# home_alarm_revB.net
KiCad netlist of a schematic drawn in EAGLE
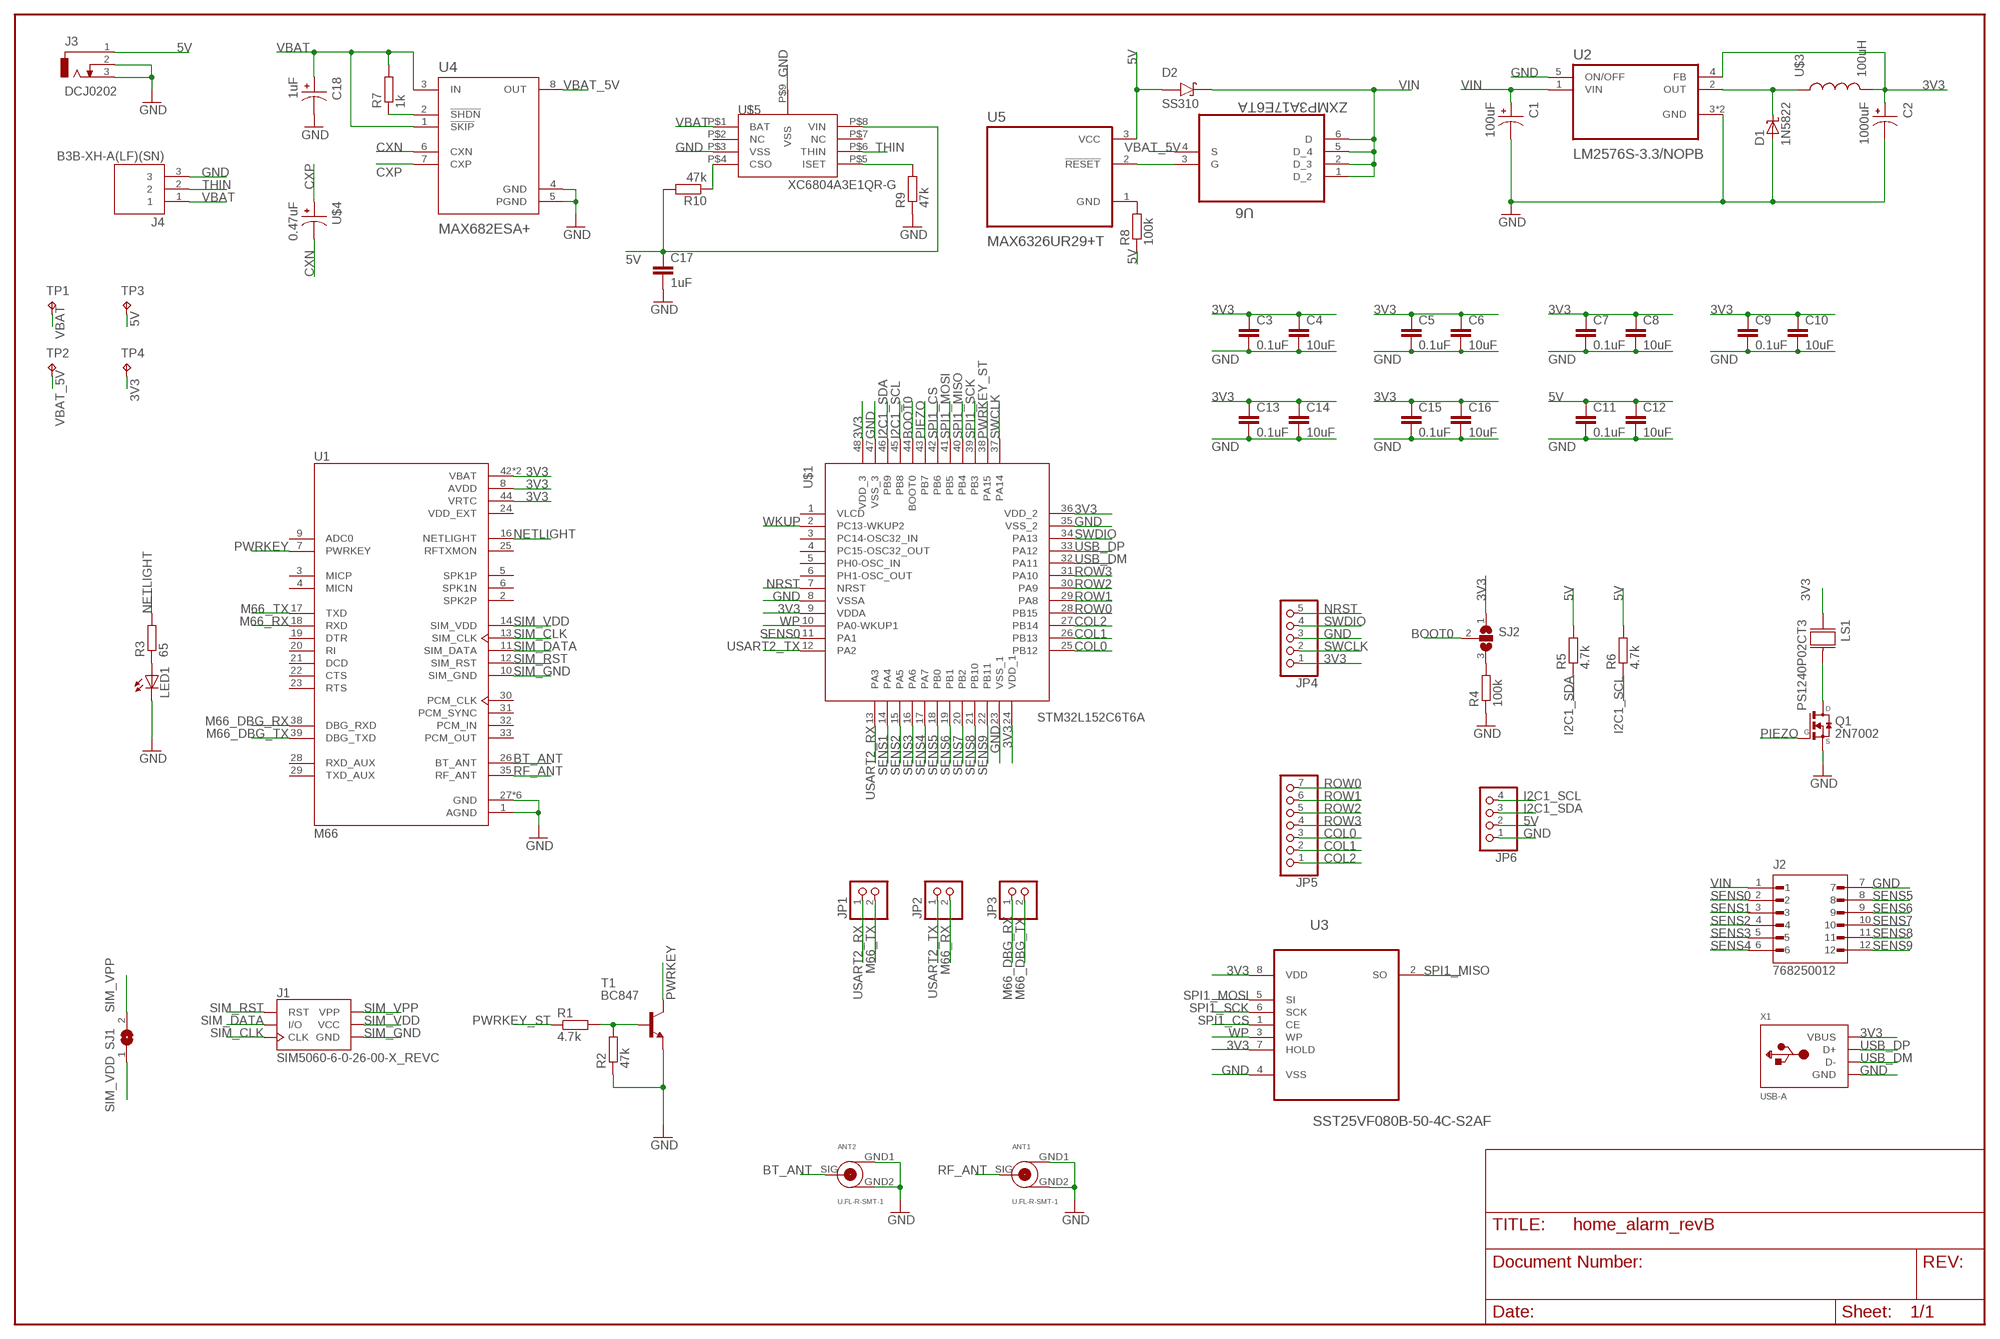
[diagram p0: schematic, sheet 1]

(export (version "E")
  (design (tool "Eeschema 10.0.6"))
  (components
    (comp (ref "ANT1")
      (value "U.FL-R-SMT-1")
      (footprint "eagle-import:U.FL-R-SMT-1")
      (fields (field (name "MF") "Hirose Electric Co Ltd"))
      (libsource (lib "eagle-import") (part "U.FL-R-SMT-1"))
    )
    (comp (ref "ANT2")
      (value "U.FL-R-SMT-1")
      (footprint "eagle-import:U.FL-R-SMT-1")
      (fields (field (name "MF") "Hirose Electric Co Ltd"))
      (libsource (lib "eagle-import") (part "U.FL-R-SMT-1"))
    )
    (comp (ref "C1")
      (value "100uF")
      (footprint "eagle-import:CAP_EEEFP1C101AV")
      (fields (field (name "MF") "Panasonic") (field (name "MP") "EEEFP1C101AV"))
      (libsource (lib "eagle-import") (part "EEEFP1C101AV"))
    )
    (comp (ref "C2")
      (value "1000uF")
      (footprint "eagle-import:CAP_EEEFK1C102SV")
      (fields (field (name "MF") "Panasonic") (field (name "MP") "EEEFK1C102SV"))
      (libsource (lib "eagle-import") (part "EEEFK1C102SV"))
    )
    (comp (ref "C3")
      (value "0.1uF")
      (footprint "eagle-import:C0805")
      (libsource (lib "eagle-import") (part "C-EUC0805"))
    )
    (comp (ref "C4")
      (value "10uF")
      (footprint "eagle-import:C0805")
      (libsource (lib "eagle-import") (part "C-EUC0805"))
    )
    (comp (ref "C5")
      (value "0.1uF")
      (footprint "eagle-import:C0805")
      (libsource (lib "eagle-import") (part "C-EUC0805"))
    )
    (comp (ref "C6")
      (value "10uF")
      (footprint "eagle-import:C0805")
      (libsource (lib "eagle-import") (part "C-EUC0805"))
    )
    (comp (ref "C7")
      (value "0.1uF")
      (footprint "eagle-import:C0805")
      (libsource (lib "eagle-import") (part "C-EUC0805"))
    )
    (comp (ref "C8")
      (value "10uF")
      (footprint "eagle-import:C0805")
      (libsource (lib "eagle-import") (part "C-EUC0805"))
    )
    (comp (ref "C9")
      (value "0.1uF")
      (footprint "eagle-import:C0805")
      (libsource (lib "eagle-import") (part "C-EUC0805"))
    )
    (comp (ref "C10")
      (value "10uF")
      (footprint "eagle-import:C0805")
      (libsource (lib "eagle-import") (part "C-EUC0805"))
    )
    (comp (ref "C11")
      (value "0.1uF")
      (footprint "eagle-import:C0805")
      (libsource (lib "eagle-import") (part "C-EUC0805"))
    )
    (comp (ref "C12")
      (value "10uF")
      (footprint "eagle-import:C0805")
      (libsource (lib "eagle-import") (part "C-EUC0805"))
    )
    (comp (ref "C13")
      (value "0.1uF")
      (footprint "eagle-import:C0805")
      (libsource (lib "eagle-import") (part "C-EUC0805"))
    )
    (comp (ref "C14")
      (value "10uF")
      (footprint "eagle-import:C0805")
      (libsource (lib "eagle-import") (part "C-EUC0805"))
    )
    (comp (ref "C15")
      (value "0.1uF")
      (footprint "eagle-import:C0805")
      (libsource (lib "eagle-import") (part "C-EUC0805"))
    )
    (comp (ref "C16")
      (value "10uF")
      (footprint "eagle-import:C0805")
      (libsource (lib "eagle-import") (part "C-EUC0805"))
    )
    (comp (ref "C17")
      (value "1uF")
      (footprint "eagle-import:C0805")
      (libsource (lib "eagle-import") (part "C-EUC0805"))
    )
    (comp (ref "C18")
      (value "1uF")
      (footprint "eagle-import:CAP_EEE1HA010NR")
      (fields (field (name "MF") "Panasonic Electronic") (field (name "MP") "EEE-1HA010NR"))
      (libsource (lib "eagle-import") (part "EEE1HA010NR"))
    )
    (comp (ref "D1")
      (value "1N5822")
      (footprint "eagle-import:DIOAD2120W130L950D530P")
      (fields (field (name "MF") "EIC"))
      (libsource (lib "eagle-import") (part "1N5822"))
    )
    (comp (ref "D2")
      (value "SS310")
      (footprint "eagle-import:DIOM6859X262N")
      (fields (field (name "MF") "Taiwan Semiconductor"))
      (libsource (lib "eagle-import") (part "SS310"))
    )
    (comp (ref "J1")
      (value "SIM5060-6-0-26-00-X_REVC")
      (footprint "eagle-import:GCT_SIM5060-6-0-26-00-X_REVC")
      (fields (field (name "MF") "Global Connector Technology") (field (name "MP") "SIM5060-6-0-26-00-A"))
      (libsource (lib "eagle-import") (part "SIM5060-6-0-26-00-X_REVC"))
    )
    (comp (ref "J2")
      (value "768250012")
      (footprint "eagle-import:MOLEX_768250012")
      (fields (field (name "MF") "Molex") (field (name "MP") "76825-0012"))
      (libsource (lib "eagle-import") (part "768250012"))
    )
    (comp (ref "J3")
      (value "DCJ0202")
      (footprint "eagle-import:DCJ0202")
      (libsource (lib "eagle-import") (part "DCJ0202"))
    )
    (comp (ref "J4")
      (value "B3B-XH-A(LF)(SN)")
      (footprint "eagle-import:JST_B3B-XH-A(LF)(SN)")
      (fields (field (name "MF") "JST Sales"))
      (libsource (lib "eagle-import") (part "B3B-XH-A(LF)(SN)"))
    )
    (comp (ref "JP1")
      (value "PINHD-1X2")
      (footprint "eagle-import:1X02")
      (libsource (lib "eagle-import") (part "PINHD-1X2"))
    )
    (comp (ref "JP2")
      (value "PINHD-1X2")
      (footprint "eagle-import:1X02")
      (libsource (lib "eagle-import") (part "PINHD-1X2"))
    )
    (comp (ref "JP3")
      (value "PINHD-1X2")
      (footprint "eagle-import:1X02")
      (libsource (lib "eagle-import") (part "PINHD-1X2"))
    )
    (comp (ref "JP4")
      (value "PINHD-1X5")
      (footprint "eagle-import:1X05")
      (libsource (lib "eagle-import") (part "PINHD-1X5"))
    )
    (comp (ref "JP5")
      (value "PINHD-1X7")
      (footprint "eagle-import:1X07")
      (libsource (lib "eagle-import") (part "PINHD-1X7"))
    )
    (comp (ref "JP6")
      (value "PINHD-1X4")
      (footprint "eagle-import:1X04")
      (libsource (lib "eagle-import") (part "PINHD-1X4"))
    )
    (comp (ref "LED1")
      (value "LEDCHIPLED_0603")
      (footprint "eagle-import:CHIPLED_0603")
      (libsource (lib "eagle-import") (part "LEDCHIPLED_0603"))
    )
    (comp (ref "LS1")
      (value "PS1240P02CT3")
      (footprint "eagle-import:XDCR_PS1240P02CT3")
      (fields (field (name "MF") "TDK"))
      (libsource (lib "eagle-import") (part "PS1240P02CT3"))
    )
    (comp (ref "Q1")
      (value "2N7002")
      (footprint "eagle-import:SOT23")
      (fields (field (name "MF") "STMicroelectronics") (field (name "MP") "2N-7002"))
      (libsource (lib "eagle-import") (part "2N7002"))
    )
    (comp (ref "R1")
      (value "4.7k")
      (footprint "eagle-import:R0805")
      (libsource (lib "eagle-import") (part "R-EU_R0805"))
    )
    (comp (ref "R2")
      (value "47k")
      (footprint "eagle-import:R0805")
      (libsource (lib "eagle-import") (part "R-EU_R0805"))
    )
    (comp (ref "R3")
      (value "65")
      (footprint "eagle-import:R0805")
      (libsource (lib "eagle-import") (part "R-EU_R0805"))
    )
    (comp (ref "R4")
      (value "100k")
      (footprint "eagle-import:R0805")
      (libsource (lib "eagle-import") (part "R-EU_R0805"))
    )
    (comp (ref "R5")
      (value "4.7k")
      (footprint "eagle-import:R0805")
      (libsource (lib "eagle-import") (part "R-EU_R0805"))
    )
    (comp (ref "R6")
      (value "4.7k")
      (footprint "eagle-import:R0805")
      (libsource (lib "eagle-import") (part "R-EU_R0805"))
    )
    (comp (ref "R7")
      (value "1k")
      (footprint "eagle-import:R0805")
      (libsource (lib "eagle-import") (part "R-EU_R0805"))
    )
    (comp (ref "R8")
      (value "100k")
      (footprint "eagle-import:R0805")
      (libsource (lib "eagle-import") (part "R-EU_R0805"))
    )
    (comp (ref "R9")
      (value "47k")
      (footprint "eagle-import:R0805")
      (libsource (lib "eagle-import") (part "R-EU_R0805"))
    )
    (comp (ref "R10")
      (value "47k")
      (footprint "eagle-import:R0805")
      (libsource (lib "eagle-import") (part "R-EU_R0805"))
    )
    (comp (ref "SJ1") (value "SJ") (footprint "eagle-import:SJ") (libsource (lib "eagle-import") (part "SJ")))
    (comp (ref "SJ2")
      (value "SJ2W")
      (footprint "eagle-import:SJ_2")
      (libsource (lib "eagle-import") (part "SJ2W"))
    )
    (comp (ref "T1")
      (value "BC847")
      (footprint "eagle-import:SOT23")
      (libsource (lib "eagle-import") (part "BC847"))
    )
    (comp (ref "TP1")
      (value "TPB1,27")
      (footprint "eagle-import:B1,27")
      (libsource (lib "eagle-import") (part "TPB1,27"))
    )
    (comp (ref "TP2")
      (value "TPB1,27")
      (footprint "eagle-import:B1,27")
      (libsource (lib "eagle-import") (part "TPB1,27"))
    )
    (comp (ref "TP3")
      (value "TPB1,27")
      (footprint "eagle-import:B1,27")
      (libsource (lib "eagle-import") (part "TPB1,27"))
    )
    (comp (ref "TP4")
      (value "TPB1,27")
      (footprint "eagle-import:B1,27")
      (libsource (lib "eagle-import") (part "TPB1,27"))
    )
    (comp (ref "U$1")
      (value "STM32L152C6T6A")
      (footprint "eagle-import:STM32L152C6T6A")
      (libsource (lib "eagle-import") (part "STM32L152C6T6A"))
    )
    (comp (ref "U$3")
      (value "100uH")
      (footprint "eagle-import:MSS1210-104KED")
      (libsource (lib "eagle-import") (part "MSS1210-104KED"))
    )
    (comp (ref "U$4")
      (value "0.47uF")
      (footprint "eagle-import:865230640004")
      (libsource (lib "eagle-import") (part "865230640004"))
    )
    (comp (ref "U$5")
      (value "XC6804A3E1QR-G")
      (footprint "eagle-import:XC6804A3E1QR-G")
      (libsource (lib "eagle-import") (part "XC6804A3E1QR-G"))
    )
    (comp (ref "U1")
      (value "M66")
      (footprint "eagle-import:XCVR_M66")
      (fields (field (name "MF") "Quectel"))
      (libsource (lib "eagle-import") (part "M66"))
    )
    (comp (ref "U2")
      (value "LM2576S-3.3/NOPB")
      (footprint "eagle-import:VREG_TPS79625KTTR")
      (fields (field (name "MF") "Texas Instruments"))
      (libsource (lib "eagle-import") (part "LM2576S-3.3/NOPB"))
    )
    (comp (ref "U3")
      (value "SST25VF080B-50-4C-S2AF")
      (footprint "eagle-import:SOIC127P790X216-8N")
      (fields (field (name "MF") "Microchip"))
      (libsource (lib "eagle-import") (part "SST25VF080B-50-4C-S2AF"))
    )
    (comp (ref "U4")
      (value "MAX682ESA+")
      (footprint "eagle-import:SOIC127P600X175-8N")
      (fields (field (name "MF") "Maxim Integrated"))
      (libsource (lib "eagle-import") (part "MAX682ESA+"))
    )
    (comp (ref "U5")
      (value "MAX6326UR29+T")
      (footprint "eagle-import:SOT95P237X112-3N")
      (fields (field (name "MF") "Maxim Integrated"))
      (libsource (lib "eagle-import") (part "MAX6326UR29+T"))
    )
    (comp (ref "U6")
      (value "ZXMP3A17E6TA")
      (footprint "eagle-import:SOT95P280X145-6N")
      (fields (field (name "MF") "Diodes Inc."))
      (libsource (lib "eagle-import") (part "ZXMP3A17E6TA"))
    )
    (comp (ref "X1")
      (value "USB-A")
      (footprint "eagle-import:MOLEX_480371000")
      (libsource (lib "eagle-import") (part "USB-A"))
    )
  )
  (nets
    (net (code "1") (name "/3V3") (class "Default")
      (node (ref "C10") (pin "1") (pinfunction "1_1") (pintype "passive"))
      (node (ref "C13") (pin "1") (pinfunction "1_1") (pintype "passive"))
      (node (ref "C14") (pin "1") (pinfunction "1_1") (pintype "passive"))
      (node (ref "C15") (pin "1") (pinfunction "1_1") (pintype "passive"))
      (node (ref "C16") (pin "1") (pinfunction "1_1") (pintype "passive"))
      (node (ref "C2") (pin "1") (pinfunction "1_1") (pintype "passive"))
      (node (ref "C3") (pin "1") (pinfunction "1_1") (pintype "passive"))
      (node (ref "C4") (pin "1") (pinfunction "1_1") (pintype "passive"))
      (node (ref "C5") (pin "1") (pinfunction "1_1") (pintype "passive"))
      (node (ref "C6") (pin "1") (pinfunction "1_1") (pintype "passive"))
      (node (ref "C7") (pin "1") (pinfunction "1_1") (pintype "passive"))
      (node (ref "C8") (pin "1") (pinfunction "1_1") (pintype "passive"))
      (node (ref "C9") (pin "1") (pinfunction "1_1") (pintype "passive"))
      (node (ref "JP4") (pin "1") (pinfunction "1_1") (pintype "passive"))
      (node (ref "LS1") (pin "1") (pinfunction "1_1") (pintype "passive"))
      (node (ref "SJ2") (pin "1") (pinfunction "1_1") (pintype "passive"))
      (node (ref "TP4") (pin "TP") (pinfunction "TP_TP") (pintype "input"))
      (node (ref "U$1") (pin "24") (pinfunction "VDD_1_24") (pintype "bidirectional"))
      (node (ref "U$1") (pin "36") (pinfunction "VDD_2_36") (pintype "bidirectional"))
      (node (ref "U$1") (pin "48") (pinfunction "VDD_3_48") (pintype "bidirectional"))
      (node (ref "U$1") (pin "9") (pinfunction "VDDA_9") (pintype "bidirectional"))
      (node (ref "U$3") (pin "P$2") (pinfunction "2_P$2") (pintype "passive"))
      (node (ref "U1") (pin "42") (pinfunction "VBAT_42") (pintype "power_in"))
      (node (ref "U1") (pin "43") (pinfunction "VBAT_43") (pintype "power_in"))
      (node (ref "U1") (pin "44") (pinfunction "VRTC_44") (pintype "power_in"))
      (node (ref "U1") (pin "8") (pinfunction "AVDD_8") (pintype "power_in"))
      (node (ref "U2") (pin "4") (pinfunction "FB_4") (pintype "output"))
      (node (ref "U3") (pin "7") (pinfunction "HOLD_7") (pintype "input"))
      (node (ref "U3") (pin "8") (pinfunction "VDD_8") (pintype "power_in"))
      (node (ref "X1") (pin "1") (pinfunction "VBUS_1") (pintype "power_in"))
    )
    (net (code "2") (name "/5V") (class "Default")
      (node (ref "C11") (pin "1") (pinfunction "1_1") (pintype "passive"))
      (node (ref "C12") (pin "1") (pinfunction "1_1") (pintype "passive"))
      (node (ref "C17") (pin "1") (pinfunction "1_1") (pintype "passive"))
      (node (ref "D2") (pin "A") (pinfunction "A_A") (pintype "passive"))
      (node (ref "J3") (pin "1") (pinfunction "1_1") (pintype "passive"))
      (node (ref "JP6") (pin "2") (pinfunction "2_2") (pintype "passive"))
      (node (ref "R10") (pin "2") (pinfunction "2_2") (pintype "passive"))
      (node (ref "R5") (pin "2") (pinfunction "2_2") (pintype "passive"))
      (node (ref "R6") (pin "2") (pinfunction "2_2") (pintype "passive"))
      (node (ref "R8") (pin "1") (pinfunction "1_1") (pintype "passive"))
      (node (ref "TP3") (pin "TP") (pinfunction "TP_TP") (pintype "input"))
      (node (ref "U$5") (pin "P$8") (pinfunction "VIN_P$8") (pintype "bidirectional"))
      (node (ref "U5") (pin "3") (pinfunction "VCC_3") (pintype "power_in"))
    )
    (net (code "3") (name "/BOOT0") (class "Default")
      (node (ref "SJ2") (pin "2") (pinfunction "2_2") (pintype "passive"))
      (node (ref "U$1") (pin "44") (pinfunction "BOOT0_44") (pintype "bidirectional"))
    )
    (net (code "4") (name "/BT_ANT") (class "Default")
      (node (ref "ANT2") (pin "SIG") (pinfunction "SIG_SIG") (pintype "bidirectional"))
      (node (ref "U1") (pin "26") (pinfunction "BT_ANT_26") (pintype "bidirectional"))
    )
    (net (code "5") (name "/COL0") (class "Default")
      (node (ref "JP5") (pin "3") (pinfunction "3_3") (pintype "passive"))
      (node (ref "U$1") (pin "25") (pinfunction "PB12_25") (pintype "bidirectional"))
    )
    (net (code "6") (name "/COL1") (class "Default")
      (node (ref "JP5") (pin "2") (pinfunction "2_2") (pintype "passive"))
      (node (ref "U$1") (pin "26") (pinfunction "PB13_26") (pintype "bidirectional"))
    )
    (net (code "7") (name "/COL2") (class "Default")
      (node (ref "JP5") (pin "1") (pinfunction "1_1") (pintype "passive"))
      (node (ref "U$1") (pin "27") (pinfunction "PB14_27") (pintype "bidirectional"))
    )
    (net (code "8") (name "/CXN") (class "Default")
      (node (ref "U$4") (pin "2") (pinfunction "2_2") (pintype "passive"))
      (node (ref "U4") (pin "6") (pinfunction "CXN_6") (pintype "passive"))
    )
    (net (code "9") (name "/CXP") (class "Default")
      (node (ref "U$4") (pin "1") (pinfunction "1_1") (pintype "passive"))
      (node (ref "U4") (pin "7") (pinfunction "CXP_7") (pintype "passive"))
    )
    (net (code "10") (name "/I2C1_SCL") (class "Default")
      (node (ref "JP6") (pin "4") (pinfunction "4_4") (pintype "passive"))
      (node (ref "R6") (pin "1") (pinfunction "1_1") (pintype "passive"))
      (node (ref "U$1") (pin "45") (pinfunction "PB8_45") (pintype "bidirectional"))
    )
    (net (code "11") (name "/I2C1_SDA") (class "Default")
      (node (ref "JP6") (pin "3") (pinfunction "3_3") (pintype "passive"))
      (node (ref "R5") (pin "1") (pinfunction "1_1") (pintype "passive"))
      (node (ref "U$1") (pin "46") (pinfunction "PB9_46") (pintype "bidirectional"))
    )
    (net (code "12") (name "/M66_DBG_RX") (class "Default")
      (node (ref "JP3") (pin "1") (pinfunction "1_1") (pintype "passive"))
      (node (ref "U1") (pin "38") (pinfunction "DBG_RXD_38") (pintype "input"))
    )
    (net (code "13") (name "/M66_DBG_TX") (class "Default")
      (node (ref "JP3") (pin "2") (pinfunction "2_2") (pintype "passive"))
      (node (ref "U1") (pin "39") (pinfunction "DBG_TXD_39") (pintype "output"))
    )
    (net (code "14") (name "/M66_RX") (class "Default")
      (node (ref "JP2") (pin "2") (pinfunction "2_2") (pintype "passive"))
      (node (ref "U1") (pin "18") (pinfunction "RXD_18") (pintype "input"))
    )
    (net (code "15") (name "/M66_TX") (class "Default")
      (node (ref "JP1") (pin "2") (pinfunction "2_2") (pintype "passive"))
      (node (ref "U1") (pin "17") (pinfunction "TXD_17") (pintype "output"))
    )
    (net (code "16") (name "/NETLIGHT") (class "Default")
      (node (ref "R3") (pin "2") (pinfunction "2_2") (pintype "passive"))
      (node (ref "U1") (pin "16") (pinfunction "NETLIGHT_16") (pintype "output"))
    )
    (net (code "17") (name "/NRST") (class "Default")
      (node (ref "JP4") (pin "5") (pinfunction "5_5") (pintype "passive"))
      (node (ref "U$1") (pin "7") (pinfunction "NRST_7") (pintype "bidirectional"))
    )
    (net (code "18") (name "/PIEZO") (class "Default")
      (node (ref "Q1") (pin "1") (pinfunction "G_1") (pintype "passive"))
      (node (ref "U$1") (pin "43") (pinfunction "PB7_43") (pintype "bidirectional"))
    )
    (net (code "19") (name "/PWRKEY") (class "Default")
      (node (ref "T1") (pin "3") (pinfunction "C_3") (pintype "passive"))
      (node (ref "U1") (pin "7") (pinfunction "PWRKEY_7") (pintype "input"))
    )
    (net (code "20") (name "/PWRKEY_ST") (class "Default")
      (node (ref "R1") (pin "1") (pinfunction "1_1") (pintype "passive"))
      (node (ref "U$1") (pin "38") (pinfunction "PA15_38") (pintype "bidirectional"))
    )
    (net (code "21") (name "/RF_ANT") (class "Default")
      (node (ref "ANT1") (pin "SIG") (pinfunction "SIG_SIG") (pintype "bidirectional"))
      (node (ref "U1") (pin "35") (pinfunction "RF_ANT_35") (pintype "bidirectional"))
    )
    (net (code "22") (name "/ROW0") (class "Default")
      (node (ref "JP5") (pin "7") (pinfunction "7_7") (pintype "passive"))
      (node (ref "U$1") (pin "28") (pinfunction "PB15_28") (pintype "bidirectional"))
    )
    (net (code "23") (name "/ROW1") (class "Default")
      (node (ref "JP5") (pin "6") (pinfunction "6_6") (pintype "passive"))
      (node (ref "U$1") (pin "29") (pinfunction "PA8_29") (pintype "bidirectional"))
    )
    (net (code "24") (name "/ROW2") (class "Default")
      (node (ref "JP5") (pin "5") (pinfunction "5_5") (pintype "passive"))
      (node (ref "U$1") (pin "30") (pinfunction "PA9_30") (pintype "bidirectional"))
    )
    (net (code "25") (name "/ROW3") (class "Default")
      (node (ref "JP5") (pin "4") (pinfunction "4_4") (pintype "passive"))
      (node (ref "U$1") (pin "31") (pinfunction "PA10_31") (pintype "bidirectional"))
    )
    (net (code "26") (name "/SENS0") (class "Default")
      (node (ref "J2") (pin "2") (pinfunction "2_2") (pintype "passive"))
      (node (ref "U$1") (pin "11") (pinfunction "PA1_11") (pintype "bidirectional"))
    )
    (net (code "27") (name "/SENS1") (class "Default")
      (node (ref "J2") (pin "3") (pinfunction "3_3") (pintype "passive"))
      (node (ref "U$1") (pin "14") (pinfunction "PA4_14") (pintype "bidirectional"))
    )
    (net (code "28") (name "/SENS2") (class "Default")
      (node (ref "J2") (pin "4") (pinfunction "4_4") (pintype "passive"))
      (node (ref "U$1") (pin "15") (pinfunction "PA5_15") (pintype "bidirectional"))
    )
    (net (code "29") (name "/SENS3") (class "Default")
      (node (ref "J2") (pin "5") (pinfunction "5_5") (pintype "passive"))
      (node (ref "U$1") (pin "16") (pinfunction "PA6_16") (pintype "bidirectional"))
    )
    (net (code "30") (name "/SENS4") (class "Default")
      (node (ref "J2") (pin "6") (pinfunction "6_6") (pintype "passive"))
      (node (ref "U$1") (pin "17") (pinfunction "PA7_17") (pintype "bidirectional"))
    )
    (net (code "31") (name "/SENS5") (class "Default")
      (node (ref "J2") (pin "8") (pinfunction "8_8") (pintype "passive"))
      (node (ref "U$1") (pin "18") (pinfunction "PB0_18") (pintype "bidirectional"))
    )
    (net (code "32") (name "/SENS6") (class "Default")
      (node (ref "J2") (pin "9") (pinfunction "9_9") (pintype "passive"))
      (node (ref "U$1") (pin "19") (pinfunction "PB1_19") (pintype "bidirectional"))
    )
    (net (code "33") (name "/SENS7") (class "Default")
      (node (ref "J2") (pin "10") (pinfunction "10_10") (pintype "passive"))
      (node (ref "U$1") (pin "20") (pinfunction "PB2_20") (pintype "bidirectional"))
    )
    (net (code "34") (name "/SENS8") (class "Default")
      (node (ref "J2") (pin "11") (pinfunction "11_11") (pintype "passive"))
      (node (ref "U$1") (pin "21") (pinfunction "PB10_21") (pintype "bidirectional"))
    )
    (net (code "35") (name "/SENS9") (class "Default")
      (node (ref "J2") (pin "12") (pinfunction "12_12") (pintype "passive"))
      (node (ref "U$1") (pin "22") (pinfunction "PB11_22") (pintype "bidirectional"))
    )
    (net (code "36") (name "/SIM_CLK") (class "Default")
      (node (ref "J1") (pin "C3") (pinfunction "CLK_C3") (pintype "bidirectional"))
      (node (ref "U1") (pin "13") (pinfunction "SIM_CLK_13") (pintype "output"))
    )
    (net (code "37") (name "/SIM_DATA") (class "Default")
      (node (ref "J1") (pin "C7") (pinfunction "I/O_C7") (pintype "bidirectional"))
      (node (ref "U1") (pin "11") (pinfunction "SIM_DATA_11") (pintype "bidirectional"))
    )
    (net (code "38") (name "/SIM_GND") (class "Default")
      (node (ref "J1") (pin "C5") (pinfunction "GND_C5") (pintype "power_in"))
      (node (ref "U1") (pin "10") (pinfunction "SIM_GND_10") (pintype "power_in"))
    )
    (net (code "39") (name "/SIM_RST") (class "Default")
      (node (ref "J1") (pin "C2") (pinfunction "RST_C2") (pintype "input"))
      (node (ref "U1") (pin "12") (pinfunction "SIM_RST_12") (pintype "output"))
    )
    (net (code "40") (name "/SIM_VDD") (class "Default")
      (node (ref "J1") (pin "C1") (pinfunction "VCC_C1") (pintype "power_in"))
      (node (ref "SJ1") (pin "1") (pinfunction "1_1") (pintype "passive"))
      (node (ref "U1") (pin "14") (pinfunction "SIM_VDD_14") (pintype "power_in"))
    )
    (net (code "41") (name "/SIM_VPP") (class "Default")
      (node (ref "J1") (pin "C6") (pinfunction "VPP_C6") (pintype "power_in"))
      (node (ref "SJ1") (pin "2") (pinfunction "2_2") (pintype "passive"))
    )
    (net (code "42") (name "/SPI1_CS") (class "Default")
      (node (ref "U$1") (pin "42") (pinfunction "PB6_42") (pintype "bidirectional"))
      (node (ref "U3") (pin "1") (pinfunction "CE_1") (pintype "input"))
    )
    (net (code "43") (name "/SPI1_MISO") (class "Default")
      (node (ref "U$1") (pin "40") (pinfunction "PB4_40") (pintype "bidirectional"))
      (node (ref "U3") (pin "2") (pinfunction "SO_2") (pintype "output"))
    )
    (net (code "44") (name "/SPI1_MOSI") (class "Default")
      (node (ref "U$1") (pin "41") (pinfunction "PB5_41") (pintype "bidirectional"))
      (node (ref "U3") (pin "5") (pinfunction "SI_5") (pintype "input"))
    )
    (net (code "45") (name "/SPI1_SCK") (class "Default")
      (node (ref "U$1") (pin "39") (pinfunction "PB3_39") (pintype "bidirectional"))
      (node (ref "U3") (pin "6") (pinfunction "SCK_6") (pintype "input"))
    )
    (net (code "46") (name "/SWCLK") (class "Default")
      (node (ref "JP4") (pin "2") (pinfunction "2_2") (pintype "passive"))
      (node (ref "U$1") (pin "37") (pinfunction "PA14_37") (pintype "bidirectional"))
    )
    (net (code "47") (name "/SWDIO") (class "Default")
      (node (ref "JP4") (pin "4") (pinfunction "4_4") (pintype "passive"))
      (node (ref "U$1") (pin "34") (pinfunction "PA13_34") (pintype "bidirectional"))
    )
    (net (code "48") (name "/THIN") (class "Default")
      (node (ref "J4") (pin "2") (pinfunction "2_2") (pintype "passive"))
      (node (ref "U$5") (pin "P$6") (pinfunction "THIN_P$6") (pintype "bidirectional"))
    )
    (net (code "49") (name "/USART2_RX") (class "Default")
      (node (ref "JP1") (pin "1") (pinfunction "1_1") (pintype "passive"))
      (node (ref "U$1") (pin "13") (pinfunction "PA3_13") (pintype "bidirectional"))
    )
    (net (code "50") (name "/USART2_TX") (class "Default")
      (node (ref "JP2") (pin "1") (pinfunction "1_1") (pintype "passive"))
      (node (ref "U$1") (pin "12") (pinfunction "PA2_12") (pintype "bidirectional"))
    )
    (net (code "51") (name "/USB_DM") (class "Default")
      (node (ref "U$1") (pin "32") (pinfunction "PA11_32") (pintype "bidirectional"))
      (node (ref "X1") (pin "2") (pinfunction "D-_2") (pintype "bidirectional"))
    )
    (net (code "52") (name "/USB_DP") (class "Default")
      (node (ref "U$1") (pin "33") (pinfunction "PA12_33") (pintype "bidirectional"))
      (node (ref "X1") (pin "3") (pinfunction "D+_3") (pintype "bidirectional"))
    )
    (net (code "53") (name "/VBAT") (class "Default")
      (node (ref "C18") (pin "1") (pinfunction "1_1") (pintype "passive"))
      (node (ref "J4") (pin "1") (pinfunction "1_1") (pintype "passive"))
      (node (ref "R7") (pin "2") (pinfunction "2_2") (pintype "passive"))
      (node (ref "TP1") (pin "TP") (pinfunction "TP_TP") (pintype "input"))
      (node (ref "U$5") (pin "P$1") (pinfunction "BAT_P$1") (pintype "bidirectional"))
      (node (ref "U4") (pin "1") (pinfunction "~{SKIP}_1") (pintype "input"))
      (node (ref "U4") (pin "3") (pinfunction "IN_3") (pintype "input"))
    )
    (net (code "54") (name "/VBAT_5V") (class "Default")
      (node (ref "TP2") (pin "TP") (pinfunction "TP_TP") (pintype "input"))
      (node (ref "U4") (pin "8") (pinfunction "OUT_8") (pintype "output"))
      (node (ref "U6") (pin "4") (pinfunction "S_4") (pintype "input"))
    )
    (net (code "55") (name "/VDD_EXT") (class "Default")
      (node (ref "U1") (pin "24") (pinfunction "VDD_EXT_24") (pintype "power_in"))
    )
    (net (code "56") (name "/VIN") (class "Default")
      (node (ref "C1") (pin "1") (pinfunction "1_1") (pintype "passive"))
      (node (ref "D2") (pin "C") (pinfunction "K_C") (pintype "passive"))
      (node (ref "J2") (pin "1") (pinfunction "1_1") (pintype "passive"))
      (node (ref "U2") (pin "1") (pinfunction "VIN_1") (pintype "input"))
      (node (ref "U6") (pin "1") (pinfunction "D_2_1") (pintype "output"))
      (node (ref "U6") (pin "2") (pinfunction "D_3_2") (pintype "output"))
      (node (ref "U6") (pin "5") (pinfunction "D_4_5") (pintype "output"))
      (node (ref "U6") (pin "6") (pinfunction "D_6") (pintype "output"))
    )
    (net (code "57") (name "/WKUP") (class "Default")
      (node (ref "U$1") (pin "2") (pinfunction "PC13-WKUP2_2") (pintype "bidirectional"))
    )
    (net (code "58") (name "/WP") (class "Default")
      (node (ref "U$1") (pin "10") (pinfunction "PA0-WKUP1_10") (pintype "bidirectional"))
      (node (ref "U3") (pin "3") (pinfunction "WP_3") (pintype "input"))
    )
    (net (code "59") (name "GND") (class "Default")
      (node (ref "ANT1") (pin "GND1") (pinfunction "GND1_GND1") (pintype "bidirectional"))
      (node (ref "ANT1") (pin "GND2") (pinfunction "GND2_GND2") (pintype "bidirectional"))
      (node (ref "ANT2") (pin "GND1") (pinfunction "GND1_GND1") (pintype "bidirectional"))
      (node (ref "ANT2") (pin "GND2") (pinfunction "GND2_GND2") (pintype "bidirectional"))
      (node (ref "C1") (pin "2") (pinfunction "2_2") (pintype "passive"))
      (node (ref "C10") (pin "2") (pinfunction "2_2") (pintype "passive"))
      (node (ref "C11") (pin "2") (pinfunction "2_2") (pintype "passive"))
      (node (ref "C12") (pin "2") (pinfunction "2_2") (pintype "passive"))
      (node (ref "C13") (pin "2") (pinfunction "2_2") (pintype "passive"))
      (node (ref "C14") (pin "2") (pinfunction "2_2") (pintype "passive"))
      (node (ref "C15") (pin "2") (pinfunction "2_2") (pintype "passive"))
      (node (ref "C16") (pin "2") (pinfunction "2_2") (pintype "passive"))
      (node (ref "C17") (pin "2") (pinfunction "2_2") (pintype "passive"))
      (node (ref "C18") (pin "2") (pinfunction "2_2") (pintype "passive"))
      (node (ref "C2") (pin "2") (pinfunction "2_2") (pintype "passive"))
      (node (ref "C3") (pin "2") (pinfunction "2_2") (pintype "passive"))
      (node (ref "C4") (pin "2") (pinfunction "2_2") (pintype "passive"))
      (node (ref "C5") (pin "2") (pinfunction "2_2") (pintype "passive"))
      (node (ref "C6") (pin "2") (pinfunction "2_2") (pintype "passive"))
      (node (ref "C7") (pin "2") (pinfunction "2_2") (pintype "passive"))
      (node (ref "C8") (pin "2") (pinfunction "2_2") (pintype "passive"))
      (node (ref "C9") (pin "2") (pinfunction "2_2") (pintype "passive"))
      (node (ref "D1") (pin "A") (pinfunction "A_A") (pintype "passive"))
      (node (ref "J2") (pin "7") (pinfunction "7_7") (pintype "passive"))
      (node (ref "J3") (pin "2") (pinfunction "2_2") (pintype "passive"))
      (node (ref "J3") (pin "3") (pinfunction "3_3") (pintype "passive"))
      (node (ref "J4") (pin "3") (pinfunction "3_3") (pintype "passive"))
      (node (ref "JP4") (pin "3") (pinfunction "3_3") (pintype "passive"))
      (node (ref "JP6") (pin "1") (pinfunction "1_1") (pintype "passive"))
      (node (ref "LED1") (pin "C") (pinfunction "C_C") (pintype "passive"))
      (node (ref "Q1") (pin "2") (pinfunction "S_2") (pintype "passive"))
      (node (ref "R2") (pin "1") (pinfunction "1_1") (pintype "passive"))
      (node (ref "R4") (pin "1") (pinfunction "1_1") (pintype "passive"))
      (node (ref "R9") (pin "1") (pinfunction "1_1") (pintype "passive"))
      (node (ref "T1") (pin "2") (pinfunction "E_2") (pintype "passive"))
      (node (ref "U$1") (pin "23") (pinfunction "VSS_1_23") (pintype "bidirectional"))
      (node (ref "U$1") (pin "35") (pinfunction "VSS_2_35") (pintype "bidirectional"))
      (node (ref "U$1") (pin "47") (pinfunction "VSS_3_47") (pintype "bidirectional"))
      (node (ref "U$1") (pin "8") (pinfunction "VSSA_8") (pintype "bidirectional"))
      (node (ref "U$5") (pin "P$3") (pinfunction "VSS_P$3") (pintype "bidirectional"))
      (node (ref "U$5") (pin "P$9") (pinfunction "VSS_P$9") (pintype "bidirectional"))
      (node (ref "U1") (pin "1") (pinfunction "AGND_1") (pintype "power_in"))
      (node (ref "U1") (pin "27") (pinfunction "GND_27") (pintype "power_in"))
      (node (ref "U1") (pin "34") (pinfunction "GND_34") (pintype "power_in"))
      (node (ref "U1") (pin "36") (pinfunction "GND_36") (pintype "power_in"))
      (node (ref "U1") (pin "37") (pinfunction "GND_37") (pintype "power_in"))
      (node (ref "U1") (pin "40") (pinfunction "GND_40") (pintype "power_in"))
      (node (ref "U1") (pin "41") (pinfunction "GND_41") (pintype "power_in"))
      (node (ref "U2") (pin "3") (pinfunction "GND_3") (pintype "power_in"))
      (node (ref "U2") (pin "5") (pinfunction "ON/OFF_5") (pintype "input"))
      (node (ref "U2") (pin "6") (pinfunction "GND_6") (pintype "power_in"))
      (node (ref "U3") (pin "4") (pinfunction "VSS_4") (pintype "passive"))
      (node (ref "U4") (pin "4") (pinfunction "GND_4") (pintype "power_in"))
      (node (ref "U4") (pin "5") (pinfunction "PGND_5") (pintype "power_in"))
      (node (ref "X1") (pin "4") (pinfunction "GND_4") (pintype "power_in"))
    )
    (net (code "60") (name "Net-(LED1-PadA)") (class "Default")
      (node (ref "LED1") (pin "A") (pinfunction "A_A") (pintype "passive"))
      (node (ref "R3") (pin "1") (pinfunction "1_1") (pintype "passive"))
    )
    (net (code "61") (name "Net-(Q1-D)") (class "Default")
      (node (ref "LS1") (pin "2") (pinfunction "2_2") (pintype "passive"))
      (node (ref "Q1") (pin "3") (pinfunction "D_3") (pintype "passive"))
    )
    (net (code "62") (name "Net-(R4-Pad2)") (class "Default")
      (node (ref "R4") (pin "2") (pinfunction "2_2") (pintype "passive"))
      (node (ref "SJ2") (pin "3") (pinfunction "3_3") (pintype "passive"))
    )
    (net (code "63") (name "Net-(T1-B)") (class "Default")
      (node (ref "R1") (pin "2") (pinfunction "2_2") (pintype "passive"))
      (node (ref "R2") (pin "2") (pinfunction "2_2") (pintype "passive"))
      (node (ref "T1") (pin "1") (pinfunction "B_1") (pintype "passive"))
    )
    (net (code "64") (name "Net-(U$3-1)") (class "Default")
      (node (ref "D1") (pin "C") (pinfunction "C_C") (pintype "passive"))
      (node (ref "U$3") (pin "P$1") (pinfunction "1_P$1") (pintype "passive"))
      (node (ref "U2") (pin "2") (pinfunction "OUT_2") (pintype "output"))
    )
    (net (code "65") (name "Net-(U$5-CSO)") (class "Default")
      (node (ref "R10") (pin "1") (pinfunction "1_1") (pintype "passive"))
      (node (ref "U$5") (pin "P$4") (pinfunction "CSO_P$4") (pintype "bidirectional"))
    )
    (net (code "66") (name "Net-(U$5-ISET)") (class "Default")
      (node (ref "R9") (pin "2") (pinfunction "2_2") (pintype "passive"))
      (node (ref "U$5") (pin "P$5") (pinfunction "ISET_P$5") (pintype "bidirectional"))
    )
    (net (code "67") (name "Net-(U4-~{SHDN})") (class "Default")
      (node (ref "R7") (pin "1") (pinfunction "1_1") (pintype "passive"))
      (node (ref "U4") (pin "2") (pinfunction "~{SHDN}_2") (pintype "input"))
    )
    (net (code "68") (name "Net-(U5-GND)") (class "Default")
      (node (ref "R8") (pin "2") (pinfunction "2_2") (pintype "passive"))
      (node (ref "U5") (pin "1") (pinfunction "GND_1") (pintype "power_in"))
    )
    (net (code "69") (name "Net-(U5-~{RESET})") (class "Default")
      (node (ref "U5") (pin "2") (pinfunction "~{RESET}_2") (pintype "output"))
      (node (ref "U6") (pin "3") (pinfunction "G_3") (pintype "input"))
    )
    (net (code "70") (name "unconnected-(U$1-PC14-OSC32_IN-Pad3)") (class "Default")
      (node (ref "U$1") (pin "3") (pinfunction "PC14-OSC32_IN_3") (pintype "bidirectional"))
    )
    (net (code "71") (name "unconnected-(U$1-PC15-OSC32_OUT-Pad4)") (class "Default")
      (node (ref "U$1") (pin "4") (pinfunction "PC15-OSC32_OUT_4") (pintype "bidirectional"))
    )
    (net (code "72") (name "unconnected-(U$1-PH0-OSC_IN-Pad5)") (class "Default")
      (node (ref "U$1") (pin "5") (pinfunction "PH0-OSC_IN_5") (pintype "bidirectional"))
    )
    (net (code "73") (name "unconnected-(U$1-PH1-OSC_OUT-Pad6)") (class "Default")
      (node (ref "U$1") (pin "6") (pinfunction "PH1-OSC_OUT_6") (pintype "bidirectional"))
    )
    (net (code "74") (name "unconnected-(U$1-VLCD-Pad1)") (class "Default")
      (node (ref "U$1") (pin "1") (pinfunction "VLCD_1") (pintype "bidirectional"))
    )
    (net (code "75") (name "unconnected-(U$5-NC-PadP$2)") (class "Default")
      (node (ref "U$5") (pin "P$2") (pinfunction "NC_P$2") (pintype "bidirectional"))
    )
    (net (code "76") (name "unconnected-(U$5-NC-PadP$7)") (class "Default")
      (node (ref "U$5") (pin "P$7") (pinfunction "NC_P$7") (pintype "bidirectional"))
    )
    (net (code "77") (name "unconnected-(U1-ADC0-Pad9)") (class "Default")
      (node (ref "U1") (pin "9") (pinfunction "ADC0_9") (pintype "input"))
    )
    (net (code "78") (name "unconnected-(U1-CTS-Pad22)") (class "Default")
      (node (ref "U1") (pin "22") (pinfunction "CTS_22") (pintype "output"))
    )
    (net (code "79") (name "unconnected-(U1-DCD-Pad21)") (class "Default")
      (node (ref "U1") (pin "21") (pinfunction "DCD_21") (pintype "output"))
    )
    (net (code "80") (name "unconnected-(U1-DTR-Pad19)") (class "Default")
      (node (ref "U1") (pin "19") (pinfunction "DTR_19") (pintype "input"))
    )
    (net (code "81") (name "unconnected-(U1-MICN-Pad4)") (class "Default")
      (node (ref "U1") (pin "4") (pinfunction "MICN_4") (pintype "input"))
    )
    (net (code "82") (name "unconnected-(U1-MICP-Pad3)") (class "Default")
      (node (ref "U1") (pin "3") (pinfunction "MICP_3") (pintype "input"))
    )
    (net (code "83") (name "unconnected-(U1-PCM_CLK-Pad30)") (class "Default")
      (node (ref "U1") (pin "30") (pinfunction "PCM_CLK_30") (pintype "output"))
    )
    (net (code "84") (name "unconnected-(U1-PCM_IN-Pad32)") (class "Default")
      (node (ref "U1") (pin "32") (pinfunction "PCM_IN_32") (pintype "input"))
    )
    (net (code "85") (name "unconnected-(U1-PCM_OUT-Pad33)") (class "Default")
      (node (ref "U1") (pin "33") (pinfunction "PCM_OUT_33") (pintype "output"))
    )
    (net (code "86") (name "unconnected-(U1-PCM_SYNC-Pad31)") (class "Default")
      (node (ref "U1") (pin "31") (pinfunction "PCM_SYNC_31") (pintype "output"))
    )
    (net (code "87") (name "unconnected-(U1-RFTXMON-Pad25)") (class "Default")
      (node (ref "U1") (pin "25") (pinfunction "RFTXMON_25") (pintype "output"))
    )
    (net (code "88") (name "unconnected-(U1-RI-Pad20)") (class "Default")
      (node (ref "U1") (pin "20") (pinfunction "RI_20") (pintype "output"))
    )
    (net (code "89") (name "unconnected-(U1-RTS-Pad23)") (class "Default")
      (node (ref "U1") (pin "23") (pinfunction "RTS_23") (pintype "input"))
    )
    (net (code "90") (name "unconnected-(U1-RXD_AUX-Pad28)") (class "Default")
      (node (ref "U1") (pin "28") (pinfunction "RXD_AUX_28") (pintype "input"))
    )
    (net (code "91") (name "unconnected-(U1-SPK1N-Pad6)") (class "Default")
      (node (ref "U1") (pin "6") (pinfunction "SPK1N_6") (pintype "output"))
    )
    (net (code "92") (name "unconnected-(U1-SPK1P-Pad5)") (class "Default")
      (node (ref "U1") (pin "5") (pinfunction "SPK1P_5") (pintype "output"))
    )
    (net (code "93") (name "unconnected-(U1-SPK2P-Pad2)") (class "Default")
      (node (ref "U1") (pin "2") (pinfunction "SPK2P_2") (pintype "output"))
    )
    (net (code "94") (name "unconnected-(U1-TXD_AUX-Pad29)") (class "Default")
      (node (ref "U1") (pin "29") (pinfunction "TXD_AUX_29") (pintype "output"))
    )
  )
)
